# board_v2.net
KiCad netlist of a schematic drawn in EAGLE
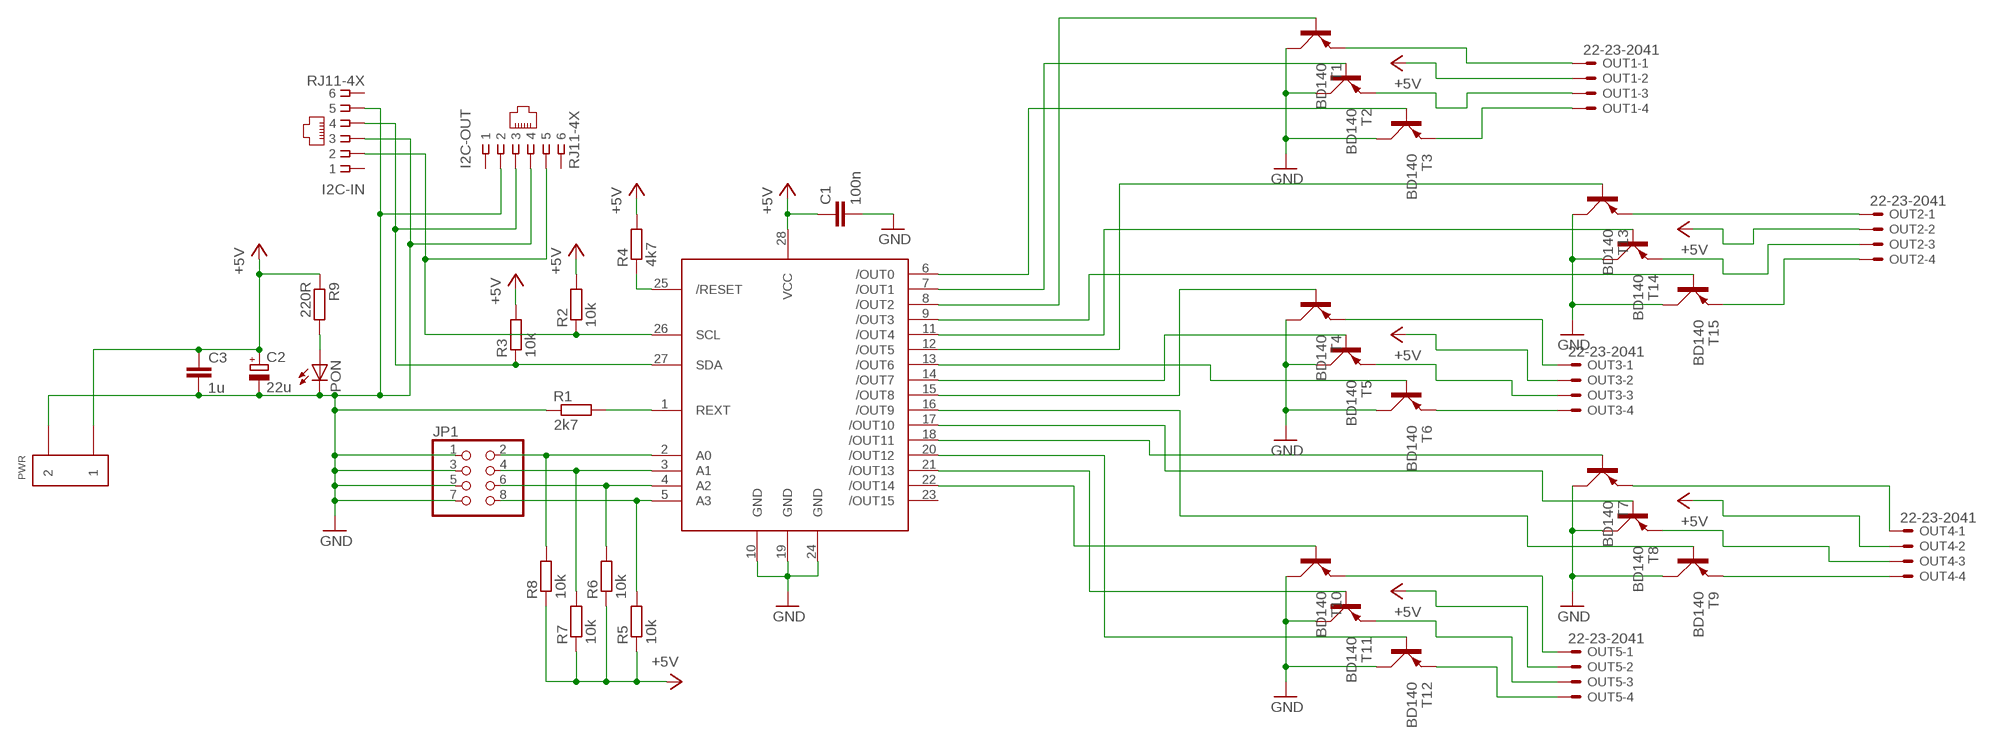
[diagram p0: schematic, sheet 1]

(export (version "E")
  (design (tool "Eeschema 10.0.6"))
  (components
    (comp (ref "C1")
      (value "100n")
      (footprint "eagle-import:C1206")
      (libsource (lib "eagle-import") (part "C-EUC1206"))
    )
    (comp (ref "C2")
      (value "22u")
      (footprint "eagle-import:E2,5-5")
      (libsource (lib "eagle-import") (part "CPOL-EUE2.5-5"))
    )
    (comp (ref "C3")
      (value "1u")
      (footprint "eagle-import:C1206")
      (libsource (lib "eagle-import") (part "C-EUC1206"))
    )
    (comp (ref "I2C-IN")
      (value "RJ11-4X")
      (footprint "eagle-import:RJ11-NO_SHIELD")
      (fields (field (name "MPN") "6609214-3"))
      (libsource (lib "eagle-import") (part "RJ11-4X"))
    )
    (comp (ref "I2C-OUT")
      (value "RJ11-4X")
      (footprint "eagle-import:RJ11-NO_SHIELD")
      (fields
        (field (name "MPN") "6609214-3")
        (field (name "MPN_1") "6609214-3")
        (field (name "OC_FARNELL") "unknown")
        (field (name "OC_NEWARK") "19R7022")
      )
      (libsource (lib "eagle-import") (part "RJ11-4X"))
    )
    (comp (ref "IC1")
      (value "TLC59116")
      (footprint "eagle-import:TSSOP28")
      (libsource (lib "eagle-import") (part "TLC59116"))
    )
    (comp (ref "JP1")
      (value "PINHD-2X4")
      (footprint "eagle-import:2X04")
      (libsource (lib "eagle-import") (part "PINHD-2X4"))
    )
    (comp (ref "OUT1")
      (value "22-23-2041")
      (footprint "eagle-import:22-23-2041")
      (fields (field (name "MF") "MOLEX"))
      (libsource (lib "eagle-import") (part "22-23-2041"))
    )
    (comp (ref "OUT2")
      (value "22-23-2041")
      (footprint "eagle-import:22-23-2041")
      (fields (field (name "MF") "MOLEX"))
      (libsource (lib "eagle-import") (part "22-23-2041"))
    )
    (comp (ref "OUT3")
      (value "22-23-2041")
      (footprint "eagle-import:22-23-2041")
      (fields (field (name "MF") "MOLEX"))
      (libsource (lib "eagle-import") (part "22-23-2041"))
    )
    (comp (ref "OUT4")
      (value "22-23-2041")
      (footprint "eagle-import:22-23-2041")
      (fields (field (name "MF") "MOLEX"))
      (libsource (lib "eagle-import") (part "22-23-2041"))
    )
    (comp (ref "OUT5")
      (value "22-23-2041")
      (footprint "eagle-import:22-23-2041")
      (fields (field (name "MF") "MOLEX"))
      (libsource (lib "eagle-import") (part "22-23-2041"))
    )
    (comp (ref "PON")
      (value "LEDCHIPLED_1206")
      (footprint "eagle-import:CHIPLED_1206")
      (libsource (lib "eagle-import") (part "LEDCHIPLED_1206"))
    )
    (comp (ref "PWR")
      (value "ARK210/2EX")
      (footprint "eagle-import:ARK210_2EX")
      (libsource (lib "eagle-import") (part "ARK210/2EX"))
    )
    (comp (ref "R1")
      (value "2k7")
      (footprint "eagle-import:R1206")
      (libsource (lib "eagle-import") (part "R-EU_R1206"))
    )
    (comp (ref "R2")
      (value "10k")
      (footprint "eagle-import:R1206")
      (libsource (lib "eagle-import") (part "R-EU_R1206"))
    )
    (comp (ref "R3")
      (value "10k")
      (footprint "eagle-import:R1206")
      (libsource (lib "eagle-import") (part "R-EU_R1206"))
    )
    (comp (ref "R4")
      (value "4k7")
      (footprint "eagle-import:R1206")
      (libsource (lib "eagle-import") (part "R-EU_R1206"))
    )
    (comp (ref "R5")
      (value "10k")
      (footprint "eagle-import:R1206")
      (libsource (lib "eagle-import") (part "R-EU_R1206"))
    )
    (comp (ref "R6")
      (value "10k")
      (footprint "eagle-import:R1206")
      (libsource (lib "eagle-import") (part "R-EU_R1206"))
    )
    (comp (ref "R7")
      (value "10k")
      (footprint "eagle-import:R1206")
      (libsource (lib "eagle-import") (part "R-EU_R1206"))
    )
    (comp (ref "R8")
      (value "10k")
      (footprint "eagle-import:R1206")
      (libsource (lib "eagle-import") (part "R-EU_R1206"))
    )
    (comp (ref "R9")
      (value "220R")
      (footprint "eagle-import:R1206")
      (libsource (lib "eagle-import") (part "R-EU_R1206"))
    )
    (comp (ref "T1")
      (value "BD140")
      (footprint "eagle-import:TO126AV")
      (libsource (lib "eagle-import") (part "BD140"))
    )
    (comp (ref "T2")
      (value "BD140")
      (footprint "eagle-import:TO126AV")
      (libsource (lib "eagle-import") (part "BD140"))
    )
    (comp (ref "T3")
      (value "BD140")
      (footprint "eagle-import:TO126AV")
      (libsource (lib "eagle-import") (part "BD140"))
    )
    (comp (ref "T4")
      (value "BD140")
      (footprint "eagle-import:TO126AV")
      (libsource (lib "eagle-import") (part "BD140"))
    )
    (comp (ref "T5")
      (value "BD140")
      (footprint "eagle-import:TO126AV")
      (libsource (lib "eagle-import") (part "BD140"))
    )
    (comp (ref "T6")
      (value "BD140")
      (footprint "eagle-import:TO126AV")
      (libsource (lib "eagle-import") (part "BD140"))
    )
    (comp (ref "T7")
      (value "BD140")
      (footprint "eagle-import:TO126AV")
      (libsource (lib "eagle-import") (part "BD140"))
    )
    (comp (ref "T8")
      (value "BD140")
      (footprint "eagle-import:TO126AV")
      (libsource (lib "eagle-import") (part "BD140"))
    )
    (comp (ref "T9")
      (value "BD140")
      (footprint "eagle-import:TO126AV")
      (libsource (lib "eagle-import") (part "BD140"))
    )
    (comp (ref "T10")
      (value "BD140")
      (footprint "eagle-import:TO126AV")
      (libsource (lib "eagle-import") (part "BD140"))
    )
    (comp (ref "T11")
      (value "BD140")
      (footprint "eagle-import:TO126AV")
      (libsource (lib "eagle-import") (part "BD140"))
    )
    (comp (ref "T12")
      (value "BD140")
      (footprint "eagle-import:TO126AV")
      (libsource (lib "eagle-import") (part "BD140"))
    )
    (comp (ref "T13")
      (value "BD140")
      (footprint "eagle-import:TO126AV")
      (libsource (lib "eagle-import") (part "BD140"))
    )
    (comp (ref "T14")
      (value "BD140")
      (footprint "eagle-import:TO126AV")
      (libsource (lib "eagle-import") (part "BD140"))
    )
    (comp (ref "T15")
      (value "BD140")
      (footprint "eagle-import:TO126AV")
      (libsource (lib "eagle-import") (part "BD140"))
    )
  )
  (nets
    (net (code "1") (name "+5V") (class "Default")
      (node (ref "C1") (pin "1") (pinfunction "1_1") (pintype "passive"))
      (node (ref "C2") (pin "+") (pinfunction "+_+") (pintype "passive"))
      (node (ref "C3") (pin "1") (pinfunction "1_1") (pintype "passive"))
      (node (ref "IC1") (pin "28") (pinfunction "VCC_28") (pintype "bidirectional"))
      (node (ref "OUT1") (pin "2") (pinfunction "S_2") (pintype "passive"))
      (node (ref "OUT2") (pin "2") (pinfunction "S_2") (pintype "passive"))
      (node (ref "OUT3") (pin "2") (pinfunction "S_2") (pintype "passive"))
      (node (ref "OUT4") (pin "2") (pinfunction "S_2") (pintype "passive"))
      (node (ref "OUT5") (pin "2") (pinfunction "S_2") (pintype "passive"))
      (node (ref "PWR") (pin "P$1") (pinfunction "1_P$1") (pintype "bidirectional"))
      (node (ref "R2") (pin "2") (pinfunction "2_2") (pintype "passive"))
      (node (ref "R3") (pin "2") (pinfunction "2_2") (pintype "passive"))
      (node (ref "R4") (pin "2") (pinfunction "2_2") (pintype "passive"))
      (node (ref "R5") (pin "1") (pinfunction "1_1") (pintype "passive"))
      (node (ref "R6") (pin "1") (pinfunction "1_1") (pintype "passive"))
      (node (ref "R7") (pin "1") (pinfunction "1_1") (pintype "passive"))
      (node (ref "R8") (pin "1") (pinfunction "1_1") (pintype "passive"))
      (node (ref "R9") (pin "1") (pinfunction "1_1") (pintype "passive"))
    )
    (net (code "2") (name "GND") (class "Default")
      (node (ref "C1") (pin "2") (pinfunction "2_2") (pintype "passive"))
      (node (ref "C2") (pin "-") (pinfunction "-_-") (pintype "passive"))
      (node (ref "C3") (pin "2") (pinfunction "2_2") (pintype "passive"))
      (node (ref "I2C-IN") (pin "3") (pinfunction "3_3") (pintype "passive"))
      (node (ref "I2C-IN") (pin "5") (pinfunction "5_5") (pintype "passive"))
      (node (ref "I2C-OUT") (pin "2") (pinfunction "2_2") (pintype "passive"))
      (node (ref "I2C-OUT") (pin "4") (pinfunction "4_4") (pintype "passive"))
      (node (ref "IC1") (pin "10") (pinfunction "GND_10") (pintype "bidirectional"))
      (node (ref "IC1") (pin "19") (pinfunction "GND_19") (pintype "bidirectional"))
      (node (ref "IC1") (pin "24") (pinfunction "GND_24") (pintype "bidirectional"))
      (node (ref "JP1") (pin "1") (pinfunction "1_1") (pintype "passive"))
      (node (ref "JP1") (pin "3") (pinfunction "3_3") (pintype "passive"))
      (node (ref "JP1") (pin "5") (pinfunction "5_5") (pintype "passive"))
      (node (ref "JP1") (pin "7") (pinfunction "7_7") (pintype "passive"))
      (node (ref "PON") (pin "C") (pinfunction "C_C") (pintype "passive"))
      (node (ref "PWR") (pin "P$2") (pinfunction "2_P$2") (pintype "bidirectional"))
      (node (ref "R1") (pin "1") (pinfunction "1_1") (pintype "passive"))
      (node (ref "T1") (pin "C") (pinfunction "C_C") (pintype "passive"))
      (node (ref "T10") (pin "C") (pinfunction "C_C") (pintype "passive"))
      (node (ref "T11") (pin "C") (pinfunction "C_C") (pintype "passive"))
      (node (ref "T12") (pin "C") (pinfunction "C_C") (pintype "passive"))
      (node (ref "T13") (pin "C") (pinfunction "C_C") (pintype "passive"))
      (node (ref "T14") (pin "C") (pinfunction "C_C") (pintype "passive"))
      (node (ref "T15") (pin "C") (pinfunction "C_C") (pintype "passive"))
      (node (ref "T2") (pin "C") (pinfunction "C_C") (pintype "passive"))
      (node (ref "T3") (pin "C") (pinfunction "C_C") (pintype "passive"))
      (node (ref "T4") (pin "C") (pinfunction "C_C") (pintype "passive"))
      (node (ref "T5") (pin "C") (pinfunction "C_C") (pintype "passive"))
      (node (ref "T6") (pin "C") (pinfunction "C_C") (pintype "passive"))
      (node (ref "T7") (pin "C") (pinfunction "C_C") (pintype "passive"))
      (node (ref "T8") (pin "C") (pinfunction "C_C") (pintype "passive"))
      (node (ref "T9") (pin "C") (pinfunction "C_C") (pintype "passive"))
    )
    (net (code "3") (name "Net-(IC1-A0)") (class "Default")
      (node (ref "IC1") (pin "2") (pinfunction "A0_2") (pintype "bidirectional"))
      (node (ref "JP1") (pin "2") (pinfunction "2_2") (pintype "passive"))
      (node (ref "R8") (pin "2") (pinfunction "2_2") (pintype "passive"))
    )
    (net (code "4") (name "Net-(IC1-A1)") (class "Default")
      (node (ref "IC1") (pin "3") (pinfunction "A1_3") (pintype "bidirectional"))
      (node (ref "JP1") (pin "4") (pinfunction "4_4") (pintype "passive"))
      (node (ref "R7") (pin "2") (pinfunction "2_2") (pintype "passive"))
    )
    (net (code "5") (name "Net-(IC1-A2)") (class "Default")
      (node (ref "IC1") (pin "4") (pinfunction "A2_4") (pintype "bidirectional"))
      (node (ref "JP1") (pin "6") (pinfunction "6_6") (pintype "passive"))
      (node (ref "R6") (pin "2") (pinfunction "2_2") (pintype "passive"))
    )
    (net (code "6") (name "Net-(IC1-A3)") (class "Default")
      (node (ref "IC1") (pin "5") (pinfunction "A3_5") (pintype "bidirectional"))
      (node (ref "JP1") (pin "8") (pinfunction "8_8") (pintype "passive"))
      (node (ref "R5") (pin "2") (pinfunction "2_2") (pintype "passive"))
    )
    (net (code "7") (name "Net-(IC1-REXT)") (class "Default")
      (node (ref "IC1") (pin "1") (pinfunction "REXT_1") (pintype "bidirectional"))
      (node (ref "R1") (pin "2") (pinfunction "2_2") (pintype "passive"))
    )
    (net (code "8") (name "Net-(IC1-SCL)") (class "Default")
      (node (ref "I2C-IN") (pin "2") (pinfunction "2_2") (pintype "passive"))
      (node (ref "I2C-OUT") (pin "5") (pinfunction "5_5") (pintype "passive"))
      (node (ref "IC1") (pin "26") (pinfunction "SCL_26") (pintype "bidirectional"))
      (node (ref "R2") (pin "1") (pinfunction "1_1") (pintype "passive"))
    )
    (net (code "9") (name "Net-(IC1-SDA)") (class "Default")
      (node (ref "I2C-IN") (pin "4") (pinfunction "4_4") (pintype "passive"))
      (node (ref "I2C-OUT") (pin "3") (pinfunction "3_3") (pintype "passive"))
      (node (ref "IC1") (pin "27") (pinfunction "SDA_27") (pintype "bidirectional"))
      (node (ref "R3") (pin "1") (pinfunction "1_1") (pintype "passive"))
    )
    (net (code "10") (name "Net-(IC1-{slash}OUT0)") (class "Default")
      (node (ref "IC1") (pin "6") (pinfunction "/OUT0_6") (pintype "bidirectional"))
      (node (ref "T3") (pin "B") (pinfunction "B_B") (pintype "passive"))
    )
    (net (code "11") (name "Net-(IC1-{slash}OUT1)") (class "Default")
      (node (ref "IC1") (pin "7") (pinfunction "/OUT1_7") (pintype "bidirectional"))
      (node (ref "T2") (pin "B") (pinfunction "B_B") (pintype "passive"))
    )
    (net (code "12") (name "Net-(IC1-{slash}OUT2)") (class "Default")
      (node (ref "IC1") (pin "8") (pinfunction "/OUT2_8") (pintype "bidirectional"))
      (node (ref "T1") (pin "B") (pinfunction "B_B") (pintype "passive"))
    )
    (net (code "13") (name "Net-(IC1-{slash}OUT3)") (class "Default")
      (node (ref "IC1") (pin "9") (pinfunction "/OUT3_9") (pintype "bidirectional"))
      (node (ref "T15") (pin "B") (pinfunction "B_B") (pintype "passive"))
    )
    (net (code "14") (name "Net-(IC1-{slash}OUT4)") (class "Default")
      (node (ref "IC1") (pin "11") (pinfunction "/OUT4_11") (pintype "bidirectional"))
      (node (ref "T14") (pin "B") (pinfunction "B_B") (pintype "passive"))
    )
    (net (code "15") (name "Net-(IC1-{slash}OUT5)") (class "Default")
      (node (ref "IC1") (pin "12") (pinfunction "/OUT5_12") (pintype "bidirectional"))
      (node (ref "T13") (pin "B") (pinfunction "B_B") (pintype "passive"))
    )
    (net (code "16") (name "Net-(IC1-{slash}OUT6)") (class "Default")
      (node (ref "IC1") (pin "13") (pinfunction "/OUT6_13") (pintype "bidirectional"))
      (node (ref "T6") (pin "B") (pinfunction "B_B") (pintype "passive"))
    )
    (net (code "17") (name "Net-(IC1-{slash}OUT7)") (class "Default")
      (node (ref "IC1") (pin "14") (pinfunction "/OUT7_14") (pintype "bidirectional"))
      (node (ref "T5") (pin "B") (pinfunction "B_B") (pintype "passive"))
    )
    (net (code "18") (name "Net-(IC1-{slash}OUT8)") (class "Default")
      (node (ref "IC1") (pin "15") (pinfunction "/OUT8_15") (pintype "bidirectional"))
      (node (ref "T4") (pin "B") (pinfunction "B_B") (pintype "passive"))
    )
    (net (code "19") (name "Net-(IC1-{slash}OUT9)") (class "Default")
      (node (ref "IC1") (pin "16") (pinfunction "/OUT9_16") (pintype "bidirectional"))
      (node (ref "T9") (pin "B") (pinfunction "B_B") (pintype "passive"))
    )
    (net (code "20") (name "Net-(IC1-{slash}OUT10)") (class "Default")
      (node (ref "IC1") (pin "17") (pinfunction "/OUT10_17") (pintype "bidirectional"))
      (node (ref "T8") (pin "B") (pinfunction "B_B") (pintype "passive"))
    )
    (net (code "21") (name "Net-(IC1-{slash}OUT11)") (class "Default")
      (node (ref "IC1") (pin "18") (pinfunction "/OUT11_18") (pintype "bidirectional"))
      (node (ref "T7") (pin "B") (pinfunction "B_B") (pintype "passive"))
    )
    (net (code "22") (name "Net-(IC1-{slash}OUT12)") (class "Default")
      (node (ref "IC1") (pin "20") (pinfunction "/OUT12_20") (pintype "bidirectional"))
      (node (ref "T12") (pin "B") (pinfunction "B_B") (pintype "passive"))
    )
    (net (code "23") (name "Net-(IC1-{slash}OUT13)") (class "Default")
      (node (ref "IC1") (pin "21") (pinfunction "/OUT13_21") (pintype "bidirectional"))
      (node (ref "T11") (pin "B") (pinfunction "B_B") (pintype "passive"))
    )
    (net (code "24") (name "Net-(IC1-{slash}OUT14)") (class "Default")
      (node (ref "IC1") (pin "22") (pinfunction "/OUT14_22") (pintype "bidirectional"))
      (node (ref "T10") (pin "B") (pinfunction "B_B") (pintype "passive"))
    )
    (net (code "25") (name "Net-(IC1-{slash}RESET)") (class "Default")
      (node (ref "IC1") (pin "25") (pinfunction "/RESET_25") (pintype "bidirectional"))
      (node (ref "R4") (pin "1") (pinfunction "1_1") (pintype "passive"))
    )
    (net (code "26") (name "Net-(OUT1A-S)") (class "Default")
      (node (ref "OUT1") (pin "1") (pinfunction "S_1") (pintype "passive"))
      (node (ref "T1") (pin "E") (pinfunction "E_E") (pintype "passive"))
    )
    (net (code "27") (name "Net-(OUT1C-S)") (class "Default")
      (node (ref "OUT1") (pin "3") (pinfunction "S_3") (pintype "passive"))
      (node (ref "T2") (pin "E") (pinfunction "E_E") (pintype "passive"))
    )
    (net (code "28") (name "Net-(OUT1D-S)") (class "Default")
      (node (ref "OUT1") (pin "4") (pinfunction "S_4") (pintype "passive"))
      (node (ref "T3") (pin "E") (pinfunction "E_E") (pintype "passive"))
    )
    (net (code "29") (name "Net-(OUT2A-S)") (class "Default")
      (node (ref "OUT2") (pin "1") (pinfunction "S_1") (pintype "passive"))
      (node (ref "T13") (pin "E") (pinfunction "E_E") (pintype "passive"))
    )
    (net (code "30") (name "Net-(OUT2C-S)") (class "Default")
      (node (ref "OUT2") (pin "3") (pinfunction "S_3") (pintype "passive"))
      (node (ref "T14") (pin "E") (pinfunction "E_E") (pintype "passive"))
    )
    (net (code "31") (name "Net-(OUT2D-S)") (class "Default")
      (node (ref "OUT2") (pin "4") (pinfunction "S_4") (pintype "passive"))
      (node (ref "T15") (pin "E") (pinfunction "E_E") (pintype "passive"))
    )
    (net (code "32") (name "Net-(OUT3A-S)") (class "Default")
      (node (ref "OUT3") (pin "1") (pinfunction "S_1") (pintype "passive"))
      (node (ref "T4") (pin "E") (pinfunction "E_E") (pintype "passive"))
    )
    (net (code "33") (name "Net-(OUT3C-S)") (class "Default")
      (node (ref "OUT3") (pin "3") (pinfunction "S_3") (pintype "passive"))
      (node (ref "T5") (pin "E") (pinfunction "E_E") (pintype "passive"))
    )
    (net (code "34") (name "Net-(OUT3D-S)") (class "Default")
      (node (ref "OUT3") (pin "4") (pinfunction "S_4") (pintype "passive"))
      (node (ref "T6") (pin "E") (pinfunction "E_E") (pintype "passive"))
    )
    (net (code "35") (name "Net-(OUT4A-S)") (class "Default")
      (node (ref "OUT4") (pin "1") (pinfunction "S_1") (pintype "passive"))
      (node (ref "T7") (pin "E") (pinfunction "E_E") (pintype "passive"))
    )
    (net (code "36") (name "Net-(OUT4C-S)") (class "Default")
      (node (ref "OUT4") (pin "3") (pinfunction "S_3") (pintype "passive"))
      (node (ref "T8") (pin "E") (pinfunction "E_E") (pintype "passive"))
    )
    (net (code "37") (name "Net-(OUT4D-S)") (class "Default")
      (node (ref "OUT4") (pin "4") (pinfunction "S_4") (pintype "passive"))
      (node (ref "T9") (pin "E") (pinfunction "E_E") (pintype "passive"))
    )
    (net (code "38") (name "Net-(OUT5A-S)") (class "Default")
      (node (ref "OUT5") (pin "1") (pinfunction "S_1") (pintype "passive"))
      (node (ref "T10") (pin "E") (pinfunction "E_E") (pintype "passive"))
    )
    (net (code "39") (name "Net-(OUT5C-S)") (class "Default")
      (node (ref "OUT5") (pin "3") (pinfunction "S_3") (pintype "passive"))
      (node (ref "T11") (pin "E") (pinfunction "E_E") (pintype "passive"))
    )
    (net (code "40") (name "Net-(OUT5D-S)") (class "Default")
      (node (ref "OUT5") (pin "4") (pinfunction "S_4") (pintype "passive"))
      (node (ref "T12") (pin "E") (pinfunction "E_E") (pintype "passive"))
    )
    (net (code "41") (name "Net-(PON-PadA)") (class "Default")
      (node (ref "PON") (pin "A") (pinfunction "A_A") (pintype "passive"))
      (node (ref "R9") (pin "2") (pinfunction "2_2") (pintype "passive"))
    )
    (net (code "42") (name "unconnected-(I2C-IN-Pad1)") (class "Default")
      (node (ref "I2C-IN") (pin "1") (pinfunction "1_1") (pintype "passive"))
    )
    (net (code "43") (name "unconnected-(I2C-IN-Pad6)") (class "Default")
      (node (ref "I2C-IN") (pin "6") (pinfunction "6_6") (pintype "passive"))
    )
    (net (code "44") (name "unconnected-(I2C-OUT-Pad1)") (class "Default")
      (node (ref "I2C-OUT") (pin "1") (pinfunction "1_1") (pintype "passive"))
    )
    (net (code "45") (name "unconnected-(I2C-OUT-Pad6)") (class "Default")
      (node (ref "I2C-OUT") (pin "6") (pinfunction "6_6") (pintype "passive"))
    )
    (net (code "46") (name "unconnected-(IC1-{slash}OUT15-Pad23)") (class "Default")
      (node (ref "IC1") (pin "23") (pinfunction "/OUT15_23") (pintype "bidirectional"))
    )
  )
)
